# SpaceVNXInterface.net
KiCad netlist of a schematic drawn in Altium Designer
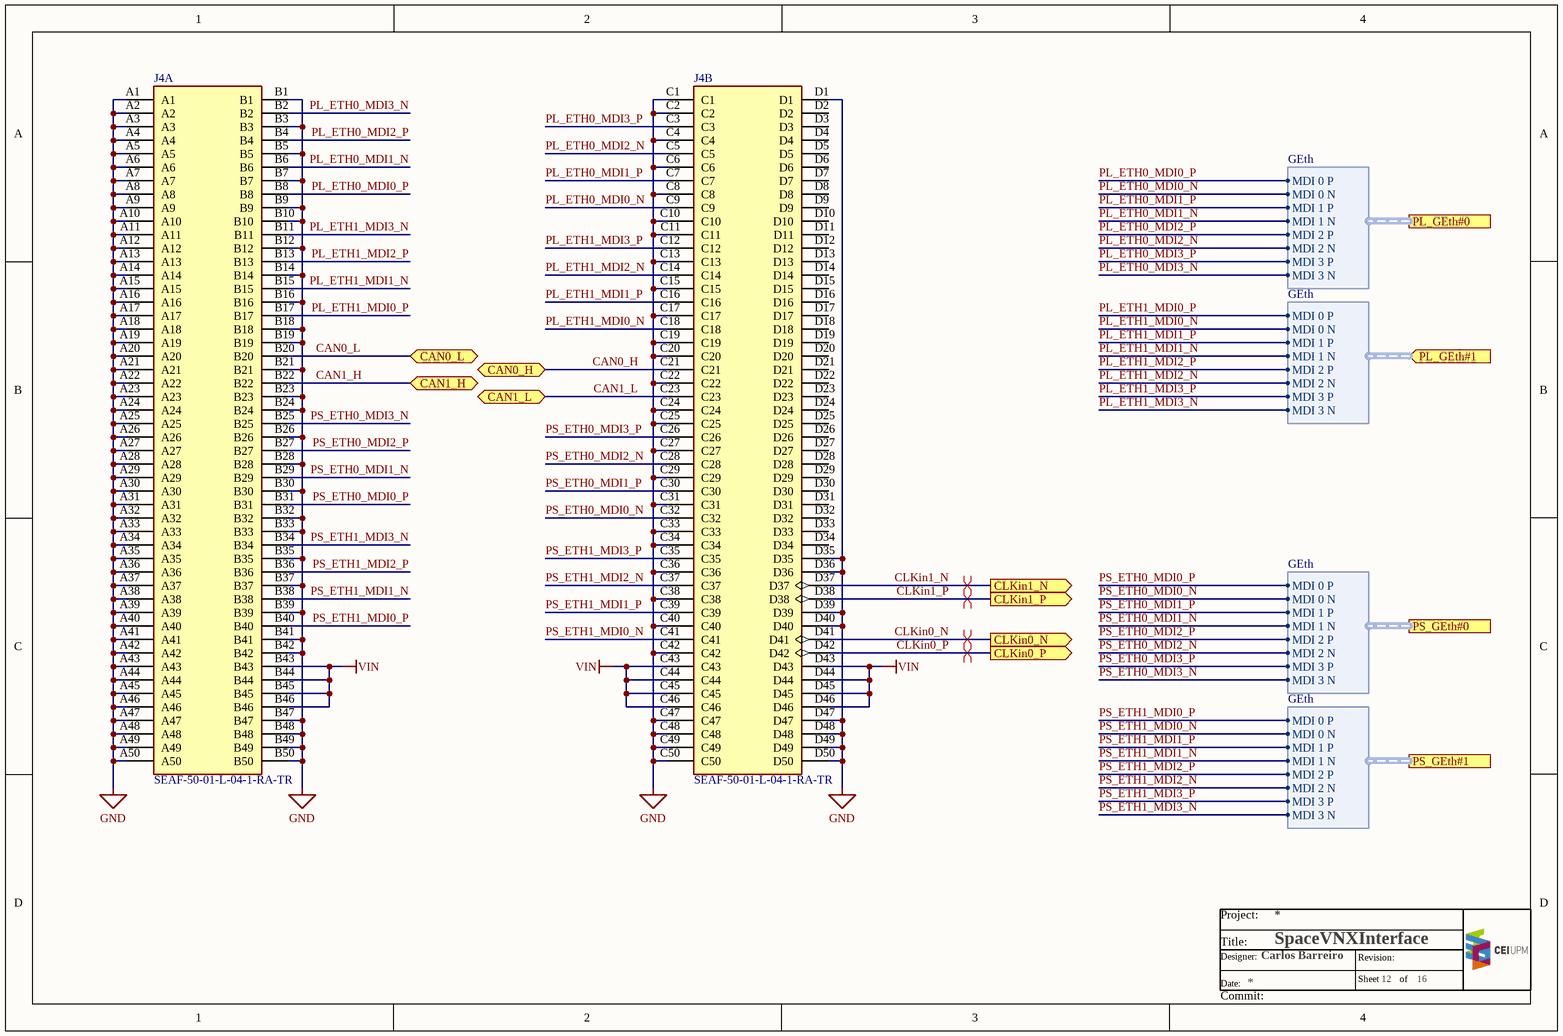
[diagram p0: SpaceVNXInterface.SchDoc]

(export (version "E")
  (design (tool "Eeschema 10.0.6"))
  (components
    (comp (ref "J4")
      (value "SEAF-50-01-L-04-1-RA-TR")
      (footprint "SAMTEC_SEAF-50-01-L-04-1-RA-TR")
      (libsource (lib "SpaceVNX") (part "SEAF-50-01-L-04-1-RA-TR"))
    )
  )
  (nets
    (net (code "2") (name "/CAN0_H") (class "Default")
      (node (ref "J4") (pin "C21") (pinfunction "C21_C21") (pintype "passive"))
    )
    (net (code "3") (name "/CAN0_L") (class "Default")
      (node (ref "J4") (pin "B20") (pinfunction "B20_B20") (pintype "passive"))
    )
    (net (code "4") (name "/CAN1_H") (class "Default")
      (node (ref "J4") (pin "B22") (pinfunction "B22_B22") (pintype "passive"))
    )
    (net (code "5") (name "/CAN1_L") (class "Default")
      (node (ref "J4") (pin "C23") (pinfunction "C23_C23") (pintype "passive"))
    )
    (net (code "6") (name "/CLKin0_N") (class "Default")
      (node (ref "J4") (pin "D41") (pinfunction "D41_D41") (pintype "passive"))
    )
    (net (code "7") (name "/CLKin0_P") (class "Default")
      (node (ref "J4") (pin "D42") (pinfunction "D42_D42") (pintype "passive"))
    )
    (net (code "8") (name "/CLKin1_N") (class "Default")
      (node (ref "J4") (pin "D37") (pinfunction "D37_D37") (pintype "passive"))
    )
    (net (code "9") (name "/CLKin1_P") (class "Default")
      (node (ref "J4") (pin "D38") (pinfunction "D38_D38") (pintype "passive"))
    )
    (net (code "10") (name "/PL_ETH0_MDI0_N") (class "Default")
      (node (ref "J4") (pin "C9") (pinfunction "C9_C9") (pintype "passive"))
    )
    (net (code "11") (name "/PL_ETH0_MDI0_P") (class "Default")
      (node (ref "J4") (pin "B8") (pinfunction "B8_B8") (pintype "passive"))
    )
    (net (code "12") (name "/PL_ETH0_MDI1_N") (class "Default")
      (node (ref "J4") (pin "B6") (pinfunction "B6_B6") (pintype "passive"))
    )
    (net (code "13") (name "/PL_ETH0_MDI1_P") (class "Default")
      (node (ref "J4") (pin "C7") (pinfunction "C7_C7") (pintype "passive"))
    )
    (net (code "14") (name "/PL_ETH0_MDI2_N") (class "Default")
      (node (ref "J4") (pin "C5") (pinfunction "C5_C5") (pintype "passive"))
    )
    (net (code "15") (name "/PL_ETH0_MDI2_P") (class "Default")
      (node (ref "J4") (pin "B4") (pinfunction "B4_B4") (pintype "passive"))
    )
    (net (code "16") (name "/PL_ETH0_MDI3_N") (class "Default")
      (node (ref "J4") (pin "B2") (pinfunction "B2_B2") (pintype "passive"))
    )
    (net (code "17") (name "/PL_ETH0_MDI3_P") (class "Default")
      (node (ref "J4") (pin "C3") (pinfunction "C3_C3") (pintype "passive"))
    )
    (net (code "18") (name "/PL_ETH1_MDI0_N") (class "Default")
      (node (ref "J4") (pin "C18") (pinfunction "C18_C18") (pintype "passive"))
    )
    (net (code "19") (name "/PL_ETH1_MDI0_P") (class "Default")
      (node (ref "J4") (pin "B17") (pinfunction "B17_B17") (pintype "passive"))
    )
    (net (code "20") (name "/PL_ETH1_MDI1_N") (class "Default")
      (node (ref "J4") (pin "B15") (pinfunction "B15_B15") (pintype "passive"))
    )
    (net (code "21") (name "/PL_ETH1_MDI1_P") (class "Default")
      (node (ref "J4") (pin "C16") (pinfunction "C16_C16") (pintype "passive"))
    )
    (net (code "22") (name "/PL_ETH1_MDI2_N") (class "Default")
      (node (ref "J4") (pin "C14") (pinfunction "C14_C14") (pintype "passive"))
    )
    (net (code "23") (name "/PL_ETH1_MDI2_P") (class "Default")
      (node (ref "J4") (pin "B13") (pinfunction "B13_B13") (pintype "passive"))
    )
    (net (code "24") (name "/PL_ETH1_MDI3_N") (class "Default")
      (node (ref "J4") (pin "B11") (pinfunction "B11_B11") (pintype "passive"))
    )
    (net (code "25") (name "/PL_ETH1_MDI3_P") (class "Default")
      (node (ref "J4") (pin "C12") (pinfunction "C12_C12") (pintype "passive"))
    )
    (net (code "26") (name "/PS_ETH0_MDI0_N") (class "Default")
      (node (ref "J4") (pin "C32") (pinfunction "C32_C32") (pintype "passive"))
    )
    (net (code "27") (name "/PS_ETH0_MDI0_P") (class "Default")
      (node (ref "J4") (pin "B31") (pinfunction "B31_B31") (pintype "passive"))
    )
    (net (code "28") (name "/PS_ETH0_MDI1_N") (class "Default")
      (node (ref "J4") (pin "B29") (pinfunction "B29_B29") (pintype "passive"))
    )
    (net (code "29") (name "/PS_ETH0_MDI1_P") (class "Default")
      (node (ref "J4") (pin "C30") (pinfunction "C30_C30") (pintype "passive"))
    )
    (net (code "30") (name "/PS_ETH0_MDI2_N") (class "Default")
      (node (ref "J4") (pin "C28") (pinfunction "C28_C28") (pintype "passive"))
    )
    (net (code "31") (name "/PS_ETH0_MDI2_P") (class "Default")
      (node (ref "J4") (pin "B27") (pinfunction "B27_B27") (pintype "passive"))
    )
    (net (code "32") (name "/PS_ETH0_MDI3_N") (class "Default")
      (node (ref "J4") (pin "B25") (pinfunction "B25_B25") (pintype "passive"))
    )
    (net (code "33") (name "/PS_ETH0_MDI3_P") (class "Default")
      (node (ref "J4") (pin "C26") (pinfunction "C26_C26") (pintype "passive"))
    )
    (net (code "34") (name "/PS_ETH1_MDI0_N") (class "Default")
      (node (ref "J4") (pin "C41") (pinfunction "C41_C41") (pintype "passive"))
    )
    (net (code "35") (name "/PS_ETH1_MDI0_P") (class "Default")
      (node (ref "J4") (pin "B40") (pinfunction "B40_B40") (pintype "passive"))
    )
    (net (code "36") (name "/PS_ETH1_MDI1_N") (class "Default")
      (node (ref "J4") (pin "B38") (pinfunction "B38_B38") (pintype "passive"))
    )
    (net (code "37") (name "/PS_ETH1_MDI1_P") (class "Default")
      (node (ref "J4") (pin "C39") (pinfunction "C39_C39") (pintype "passive"))
    )
    (net (code "38") (name "/PS_ETH1_MDI2_N") (class "Default")
      (node (ref "J4") (pin "C37") (pinfunction "C37_C37") (pintype "passive"))
    )
    (net (code "39") (name "/PS_ETH1_MDI2_P") (class "Default")
      (node (ref "J4") (pin "B36") (pinfunction "B36_B36") (pintype "passive"))
    )
    (net (code "40") (name "/PS_ETH1_MDI3_N") (class "Default")
      (node (ref "J4") (pin "B34") (pinfunction "B34_B34") (pintype "passive"))
    )
    (net (code "41") (name "/PS_ETH1_MDI3_P") (class "Default")
      (node (ref "J4") (pin "C35") (pinfunction "C35_C35") (pintype "passive"))
    )
    (net (code "43") (name "GND") (class "Default")
      (node (ref "J4") (pin "A1") (pinfunction "A1_A1") (pintype "passive"))
      (node (ref "J4") (pin "A10") (pinfunction "A10_A10") (pintype "passive"))
      (node (ref "J4") (pin "A11") (pinfunction "A11_A11") (pintype "passive"))
      (node (ref "J4") (pin "A12") (pinfunction "A12_A12") (pintype "passive"))
      (node (ref "J4") (pin "A13") (pinfunction "A13_A13") (pintype "passive"))
      (node (ref "J4") (pin "A14") (pinfunction "A14_A14") (pintype "passive"))
      (node (ref "J4") (pin "A15") (pinfunction "A15_A15") (pintype "passive"))
      (node (ref "J4") (pin "A16") (pinfunction "A16_A16") (pintype "passive"))
      (node (ref "J4") (pin "A17") (pinfunction "A17_A17") (pintype "passive"))
      (node (ref "J4") (pin "A18") (pinfunction "A18_A18") (pintype "passive"))
      (node (ref "J4") (pin "A19") (pinfunction "A19_A19") (pintype "passive"))
      (node (ref "J4") (pin "A2") (pinfunction "A2_A2") (pintype "passive"))
      (node (ref "J4") (pin "A20") (pinfunction "A20_A20") (pintype "passive"))
      (node (ref "J4") (pin "A21") (pinfunction "A21_A21") (pintype "passive"))
      (node (ref "J4") (pin "A22") (pinfunction "A22_A22") (pintype "passive"))
      (node (ref "J4") (pin "A23") (pinfunction "A23_A23") (pintype "passive"))
      (node (ref "J4") (pin "A24") (pinfunction "A24_A24") (pintype "passive"))
      (node (ref "J4") (pin "A25") (pinfunction "A25_A25") (pintype "passive"))
      (node (ref "J4") (pin "A26") (pinfunction "A26_A26") (pintype "passive"))
      (node (ref "J4") (pin "A27") (pinfunction "A27_A27") (pintype "passive"))
      (node (ref "J4") (pin "A28") (pinfunction "A28_A28") (pintype "passive"))
      (node (ref "J4") (pin "A29") (pinfunction "A29_A29") (pintype "passive"))
      (node (ref "J4") (pin "A3") (pinfunction "A3_A3") (pintype "passive"))
      (node (ref "J4") (pin "A30") (pinfunction "A30_A30") (pintype "passive"))
      (node (ref "J4") (pin "A31") (pinfunction "A31_A31") (pintype "passive"))
      (node (ref "J4") (pin "A32") (pinfunction "A32_A32") (pintype "passive"))
      (node (ref "J4") (pin "A33") (pinfunction "A33_A33") (pintype "passive"))
      (node (ref "J4") (pin "A34") (pinfunction "A34_A34") (pintype "passive"))
      (node (ref "J4") (pin "A35") (pinfunction "A35_A35") (pintype "passive"))
      (node (ref "J4") (pin "A36") (pinfunction "A36_A36") (pintype "passive"))
      (node (ref "J4") (pin "A37") (pinfunction "A37_A37") (pintype "passive"))
      (node (ref "J4") (pin "A38") (pinfunction "A38_A38") (pintype "passive"))
      (node (ref "J4") (pin "A39") (pinfunction "A39_A39") (pintype "passive"))
      (node (ref "J4") (pin "A4") (pinfunction "A4_A4") (pintype "passive"))
      (node (ref "J4") (pin "A40") (pinfunction "A40_A40") (pintype "passive"))
      (node (ref "J4") (pin "A41") (pinfunction "A41_A41") (pintype "passive"))
      (node (ref "J4") (pin "A42") (pinfunction "A42_A42") (pintype "passive"))
      (node (ref "J4") (pin "A43") (pinfunction "A43_A43") (pintype "passive"))
      (node (ref "J4") (pin "A44") (pinfunction "A44_A44") (pintype "passive"))
      (node (ref "J4") (pin "A45") (pinfunction "A45_A45") (pintype "passive"))
      (node (ref "J4") (pin "A46") (pinfunction "A46_A46") (pintype "passive"))
      (node (ref "J4") (pin "A47") (pinfunction "A47_A47") (pintype "passive"))
      (node (ref "J4") (pin "A48") (pinfunction "A48_A48") (pintype "passive"))
      (node (ref "J4") (pin "A49") (pinfunction "A49_A49") (pintype "passive"))
      (node (ref "J4") (pin "A5") (pinfunction "A5_A5") (pintype "passive"))
      (node (ref "J4") (pin "A50") (pinfunction "A50_A50") (pintype "passive"))
      (node (ref "J4") (pin "A6") (pinfunction "A6_A6") (pintype "passive"))
      (node (ref "J4") (pin "A7") (pinfunction "A7_A7") (pintype "passive"))
      (node (ref "J4") (pin "A8") (pinfunction "A8_A8") (pintype "passive"))
      (node (ref "J4") (pin "A9") (pinfunction "A9_A9") (pintype "passive"))
      (node (ref "J4") (pin "B1") (pinfunction "B1_B1") (pintype "passive"))
      (node (ref "J4") (pin "B10") (pinfunction "B10_B10") (pintype "passive"))
      (node (ref "J4") (pin "B12") (pinfunction "B12_B12") (pintype "passive"))
      (node (ref "J4") (pin "B14") (pinfunction "B14_B14") (pintype "passive"))
      (node (ref "J4") (pin "B16") (pinfunction "B16_B16") (pintype "passive"))
      (node (ref "J4") (pin "B18") (pinfunction "B18_B18") (pintype "passive"))
      (node (ref "J4") (pin "B19") (pinfunction "B19_B19") (pintype "passive"))
      (node (ref "J4") (pin "B21") (pinfunction "B21_B21") (pintype "passive"))
      (node (ref "J4") (pin "B23") (pinfunction "B23_B23") (pintype "passive"))
      (node (ref "J4") (pin "B24") (pinfunction "B24_B24") (pintype "passive"))
      (node (ref "J4") (pin "B26") (pinfunction "B26_B26") (pintype "passive"))
      (node (ref "J4") (pin "B28") (pinfunction "B28_B28") (pintype "passive"))
      (node (ref "J4") (pin "B3") (pinfunction "B3_B3") (pintype "passive"))
      (node (ref "J4") (pin "B30") (pinfunction "B30_B30") (pintype "passive"))
      (node (ref "J4") (pin "B32") (pinfunction "B32_B32") (pintype "passive"))
      (node (ref "J4") (pin "B33") (pinfunction "B33_B33") (pintype "passive"))
      (node (ref "J4") (pin "B35") (pinfunction "B35_B35") (pintype "passive"))
      (node (ref "J4") (pin "B37") (pinfunction "B37_B37") (pintype "passive"))
      (node (ref "J4") (pin "B39") (pinfunction "B39_B39") (pintype "passive"))
      (node (ref "J4") (pin "B41") (pinfunction "B41_B41") (pintype "passive"))
      (node (ref "J4") (pin "B42") (pinfunction "B42_B42") (pintype "passive"))
      (node (ref "J4") (pin "B47") (pinfunction "B47_B47") (pintype "passive"))
      (node (ref "J4") (pin "B48") (pinfunction "B48_B48") (pintype "passive"))
      (node (ref "J4") (pin "B49") (pinfunction "B49_B49") (pintype "passive"))
      (node (ref "J4") (pin "B5") (pinfunction "B5_B5") (pintype "passive"))
      (node (ref "J4") (pin "B50") (pinfunction "B50_B50") (pintype "passive"))
      (node (ref "J4") (pin "B7") (pinfunction "B7_B7") (pintype "passive"))
      (node (ref "J4") (pin "B9") (pinfunction "B9_B9") (pintype "passive"))
      (node (ref "J4") (pin "C1") (pinfunction "C1_C1") (pintype "passive"))
      (node (ref "J4") (pin "C10") (pinfunction "C10_C10") (pintype "passive"))
      (node (ref "J4") (pin "C11") (pinfunction "C11_C11") (pintype "passive"))
      (node (ref "J4") (pin "C13") (pinfunction "C13_C13") (pintype "passive"))
      (node (ref "J4") (pin "C15") (pinfunction "C15_C15") (pintype "passive"))
      (node (ref "J4") (pin "C17") (pinfunction "C17_C17") (pintype "passive"))
      (node (ref "J4") (pin "C19") (pinfunction "C19_C19") (pintype "passive"))
      (node (ref "J4") (pin "C2") (pinfunction "C2_C2") (pintype "passive"))
      (node (ref "J4") (pin "C20") (pinfunction "C20_C20") (pintype "passive"))
      (node (ref "J4") (pin "C22") (pinfunction "C22_C22") (pintype "passive"))
      (node (ref "J4") (pin "C24") (pinfunction "C24_C24") (pintype "passive"))
      (node (ref "J4") (pin "C25") (pinfunction "C25_C25") (pintype "passive"))
      (node (ref "J4") (pin "C27") (pinfunction "C27_C27") (pintype "passive"))
      (node (ref "J4") (pin "C29") (pinfunction "C29_C29") (pintype "passive"))
      (node (ref "J4") (pin "C31") (pinfunction "C31_C31") (pintype "passive"))
      (node (ref "J4") (pin "C33") (pinfunction "C33_C33") (pintype "passive"))
      (node (ref "J4") (pin "C34") (pinfunction "C34_C34") (pintype "passive"))
      (node (ref "J4") (pin "C36") (pinfunction "C36_C36") (pintype "passive"))
      (node (ref "J4") (pin "C38") (pinfunction "C38_C38") (pintype "passive"))
      (node (ref "J4") (pin "C4") (pinfunction "C4_C4") (pintype "passive"))
      (node (ref "J4") (pin "C40") (pinfunction "C40_C40") (pintype "passive"))
      (node (ref "J4") (pin "C42") (pinfunction "C42_C42") (pintype "passive"))
      (node (ref "J4") (pin "C47") (pinfunction "C47_C47") (pintype "passive"))
      (node (ref "J4") (pin "C48") (pinfunction "C48_C48") (pintype "passive"))
      (node (ref "J4") (pin "C49") (pinfunction "C49_C49") (pintype "passive"))
      (node (ref "J4") (pin "C50") (pinfunction "C50_C50") (pintype "passive"))
      (node (ref "J4") (pin "C6") (pinfunction "C6_C6") (pintype "passive"))
      (node (ref "J4") (pin "C8") (pinfunction "C8_C8") (pintype "passive"))
      (node (ref "J4") (pin "D1") (pinfunction "D1_D1") (pintype "passive"))
      (node (ref "J4") (pin "D35") (pinfunction "D35_D35") (pintype "passive"))
      (node (ref "J4") (pin "D36") (pinfunction "D36_D36") (pintype "passive"))
      (node (ref "J4") (pin "D39") (pinfunction "D39_D39") (pintype "passive"))
      (node (ref "J4") (pin "D40") (pinfunction "D40_D40") (pintype "passive"))
      (node (ref "J4") (pin "D47") (pinfunction "D47_D47") (pintype "passive"))
      (node (ref "J4") (pin "D48") (pinfunction "D48_D48") (pintype "passive"))
      (node (ref "J4") (pin "D49") (pinfunction "D49_D49") (pintype "passive"))
      (node (ref "J4") (pin "D50") (pinfunction "D50_D50") (pintype "passive"))
    )
    (net (code "44") (name "VIN") (class "Default")
      (node (ref "J4") (pin "B43") (pinfunction "B43_B43") (pintype "passive"))
      (node (ref "J4") (pin "B44") (pinfunction "B44_B44") (pintype "passive"))
      (node (ref "J4") (pin "B45") (pinfunction "B45_B45") (pintype "passive"))
      (node (ref "J4") (pin "B46") (pinfunction "B46_B46") (pintype "passive"))
      (node (ref "J4") (pin "C43") (pinfunction "C43_C43") (pintype "passive"))
      (node (ref "J4") (pin "C44") (pinfunction "C44_C44") (pintype "passive"))
      (node (ref "J4") (pin "C45") (pinfunction "C45_C45") (pintype "passive"))
      (node (ref "J4") (pin "C46") (pinfunction "C46_C46") (pintype "passive"))
      (node (ref "J4") (pin "D43") (pinfunction "D43_D43") (pintype "passive"))
      (node (ref "J4") (pin "D44") (pinfunction "D44_D44") (pintype "passive"))
      (node (ref "J4") (pin "D45") (pinfunction "D45_D45") (pintype "passive"))
      (node (ref "J4") (pin "D46") (pinfunction "D46_D46") (pintype "passive"))
    )
    (net (code "45") (name "unconnected-(J4-PadD2)") (class "Default")
      (node (ref "J4") (pin "D2") (pinfunction "D2_D2") (pintype "passive"))
    )
    (net (code "46") (name "unconnected-(J4-PadD3)") (class "Default")
      (node (ref "J4") (pin "D3") (pinfunction "D3_D3") (pintype "passive"))
    )
    (net (code "47") (name "unconnected-(J4-PadD4)") (class "Default")
      (node (ref "J4") (pin "D4") (pinfunction "D4_D4") (pintype "passive"))
    )
    (net (code "48") (name "unconnected-(J4-PadD5)") (class "Default")
      (node (ref "J4") (pin "D5") (pinfunction "D5_D5") (pintype "passive"))
    )
    (net (code "49") (name "unconnected-(J4-PadD6)") (class "Default")
      (node (ref "J4") (pin "D6") (pinfunction "D6_D6") (pintype "passive"))
    )
    (net (code "50") (name "unconnected-(J4-PadD7)") (class "Default")
      (node (ref "J4") (pin "D7") (pinfunction "D7_D7") (pintype "passive"))
    )
    (net (code "51") (name "unconnected-(J4-PadD8)") (class "Default")
      (node (ref "J4") (pin "D8") (pinfunction "D8_D8") (pintype "passive"))
    )
    (net (code "52") (name "unconnected-(J4-PadD9)") (class "Default")
      (node (ref "J4") (pin "D9") (pinfunction "D9_D9") (pintype "passive"))
    )
    (net (code "53") (name "unconnected-(J4-PadD10)") (class "Default")
      (node (ref "J4") (pin "D10") (pinfunction "D10_D10") (pintype "passive"))
    )
    (net (code "54") (name "unconnected-(J4-PadD11)") (class "Default")
      (node (ref "J4") (pin "D11") (pinfunction "D11_D11") (pintype "passive"))
    )
    (net (code "55") (name "unconnected-(J4-PadD12)") (class "Default")
      (node (ref "J4") (pin "D12") (pinfunction "D12_D12") (pintype "passive"))
    )
    (net (code "56") (name "unconnected-(J4-PadD13)") (class "Default")
      (node (ref "J4") (pin "D13") (pinfunction "D13_D13") (pintype "passive"))
    )
    (net (code "57") (name "unconnected-(J4-PadD14)") (class "Default")
      (node (ref "J4") (pin "D14") (pinfunction "D14_D14") (pintype "passive"))
    )
    (net (code "58") (name "unconnected-(J4-PadD15)") (class "Default")
      (node (ref "J4") (pin "D15") (pinfunction "D15_D15") (pintype "passive"))
    )
    (net (code "59") (name "unconnected-(J4-PadD16)") (class "Default")
      (node (ref "J4") (pin "D16") (pinfunction "D16_D16") (pintype "passive"))
    )
    (net (code "60") (name "unconnected-(J4-PadD17)") (class "Default")
      (node (ref "J4") (pin "D17") (pinfunction "D17_D17") (pintype "passive"))
    )
    (net (code "61") (name "unconnected-(J4-PadD18)") (class "Default")
      (node (ref "J4") (pin "D18") (pinfunction "D18_D18") (pintype "passive"))
    )
    (net (code "62") (name "unconnected-(J4-PadD19)") (class "Default")
      (node (ref "J4") (pin "D19") (pinfunction "D19_D19") (pintype "passive"))
    )
    (net (code "63") (name "unconnected-(J4-PadD20)") (class "Default")
      (node (ref "J4") (pin "D20") (pinfunction "D20_D20") (pintype "passive"))
    )
    (net (code "64") (name "unconnected-(J4-PadD21)") (class "Default")
      (node (ref "J4") (pin "D21") (pinfunction "D21_D21") (pintype "passive"))
    )
    (net (code "65") (name "unconnected-(J4-PadD22)") (class "Default")
      (node (ref "J4") (pin "D22") (pinfunction "D22_D22") (pintype "passive"))
    )
    (net (code "66") (name "unconnected-(J4-PadD23)") (class "Default")
      (node (ref "J4") (pin "D23") (pinfunction "D23_D23") (pintype "passive"))
    )
    (net (code "67") (name "unconnected-(J4-PadD24)") (class "Default")
      (node (ref "J4") (pin "D24") (pinfunction "D24_D24") (pintype "passive"))
    )
    (net (code "68") (name "unconnected-(J4-PadD25)") (class "Default")
      (node (ref "J4") (pin "D25") (pinfunction "D25_D25") (pintype "passive"))
    )
    (net (code "69") (name "unconnected-(J4-PadD26)") (class "Default")
      (node (ref "J4") (pin "D26") (pinfunction "D26_D26") (pintype "passive"))
    )
    (net (code "70") (name "unconnected-(J4-PadD27)") (class "Default")
      (node (ref "J4") (pin "D27") (pinfunction "D27_D27") (pintype "passive"))
    )
    (net (code "71") (name "unconnected-(J4-PadD28)") (class "Default")
      (node (ref "J4") (pin "D28") (pinfunction "D28_D28") (pintype "passive"))
    )
    (net (code "72") (name "unconnected-(J4-PadD29)") (class "Default")
      (node (ref "J4") (pin "D29") (pinfunction "D29_D29") (pintype "passive"))
    )
    (net (code "73") (name "unconnected-(J4-PadD30)") (class "Default")
      (node (ref "J4") (pin "D30") (pinfunction "D30_D30") (pintype "passive"))
    )
    (net (code "74") (name "unconnected-(J4-PadD31)") (class "Default")
      (node (ref "J4") (pin "D31") (pinfunction "D31_D31") (pintype "passive"))
    )
    (net (code "75") (name "unconnected-(J4-PadD32)") (class "Default")
      (node (ref "J4") (pin "D32") (pinfunction "D32_D32") (pintype "passive"))
    )
    (net (code "76") (name "unconnected-(J4-PadD33)") (class "Default")
      (node (ref "J4") (pin "D33") (pinfunction "D33_D33") (pintype "passive"))
    )
    (net (code "77") (name "unconnected-(J4-PadD34)") (class "Default")
      (node (ref "J4") (pin "D34") (pinfunction "D34_D34") (pintype "passive"))
    )
  )
)
